# WX0_008_511DL_4.net
KiCad netlist of a schematic drawn in Altium Designer
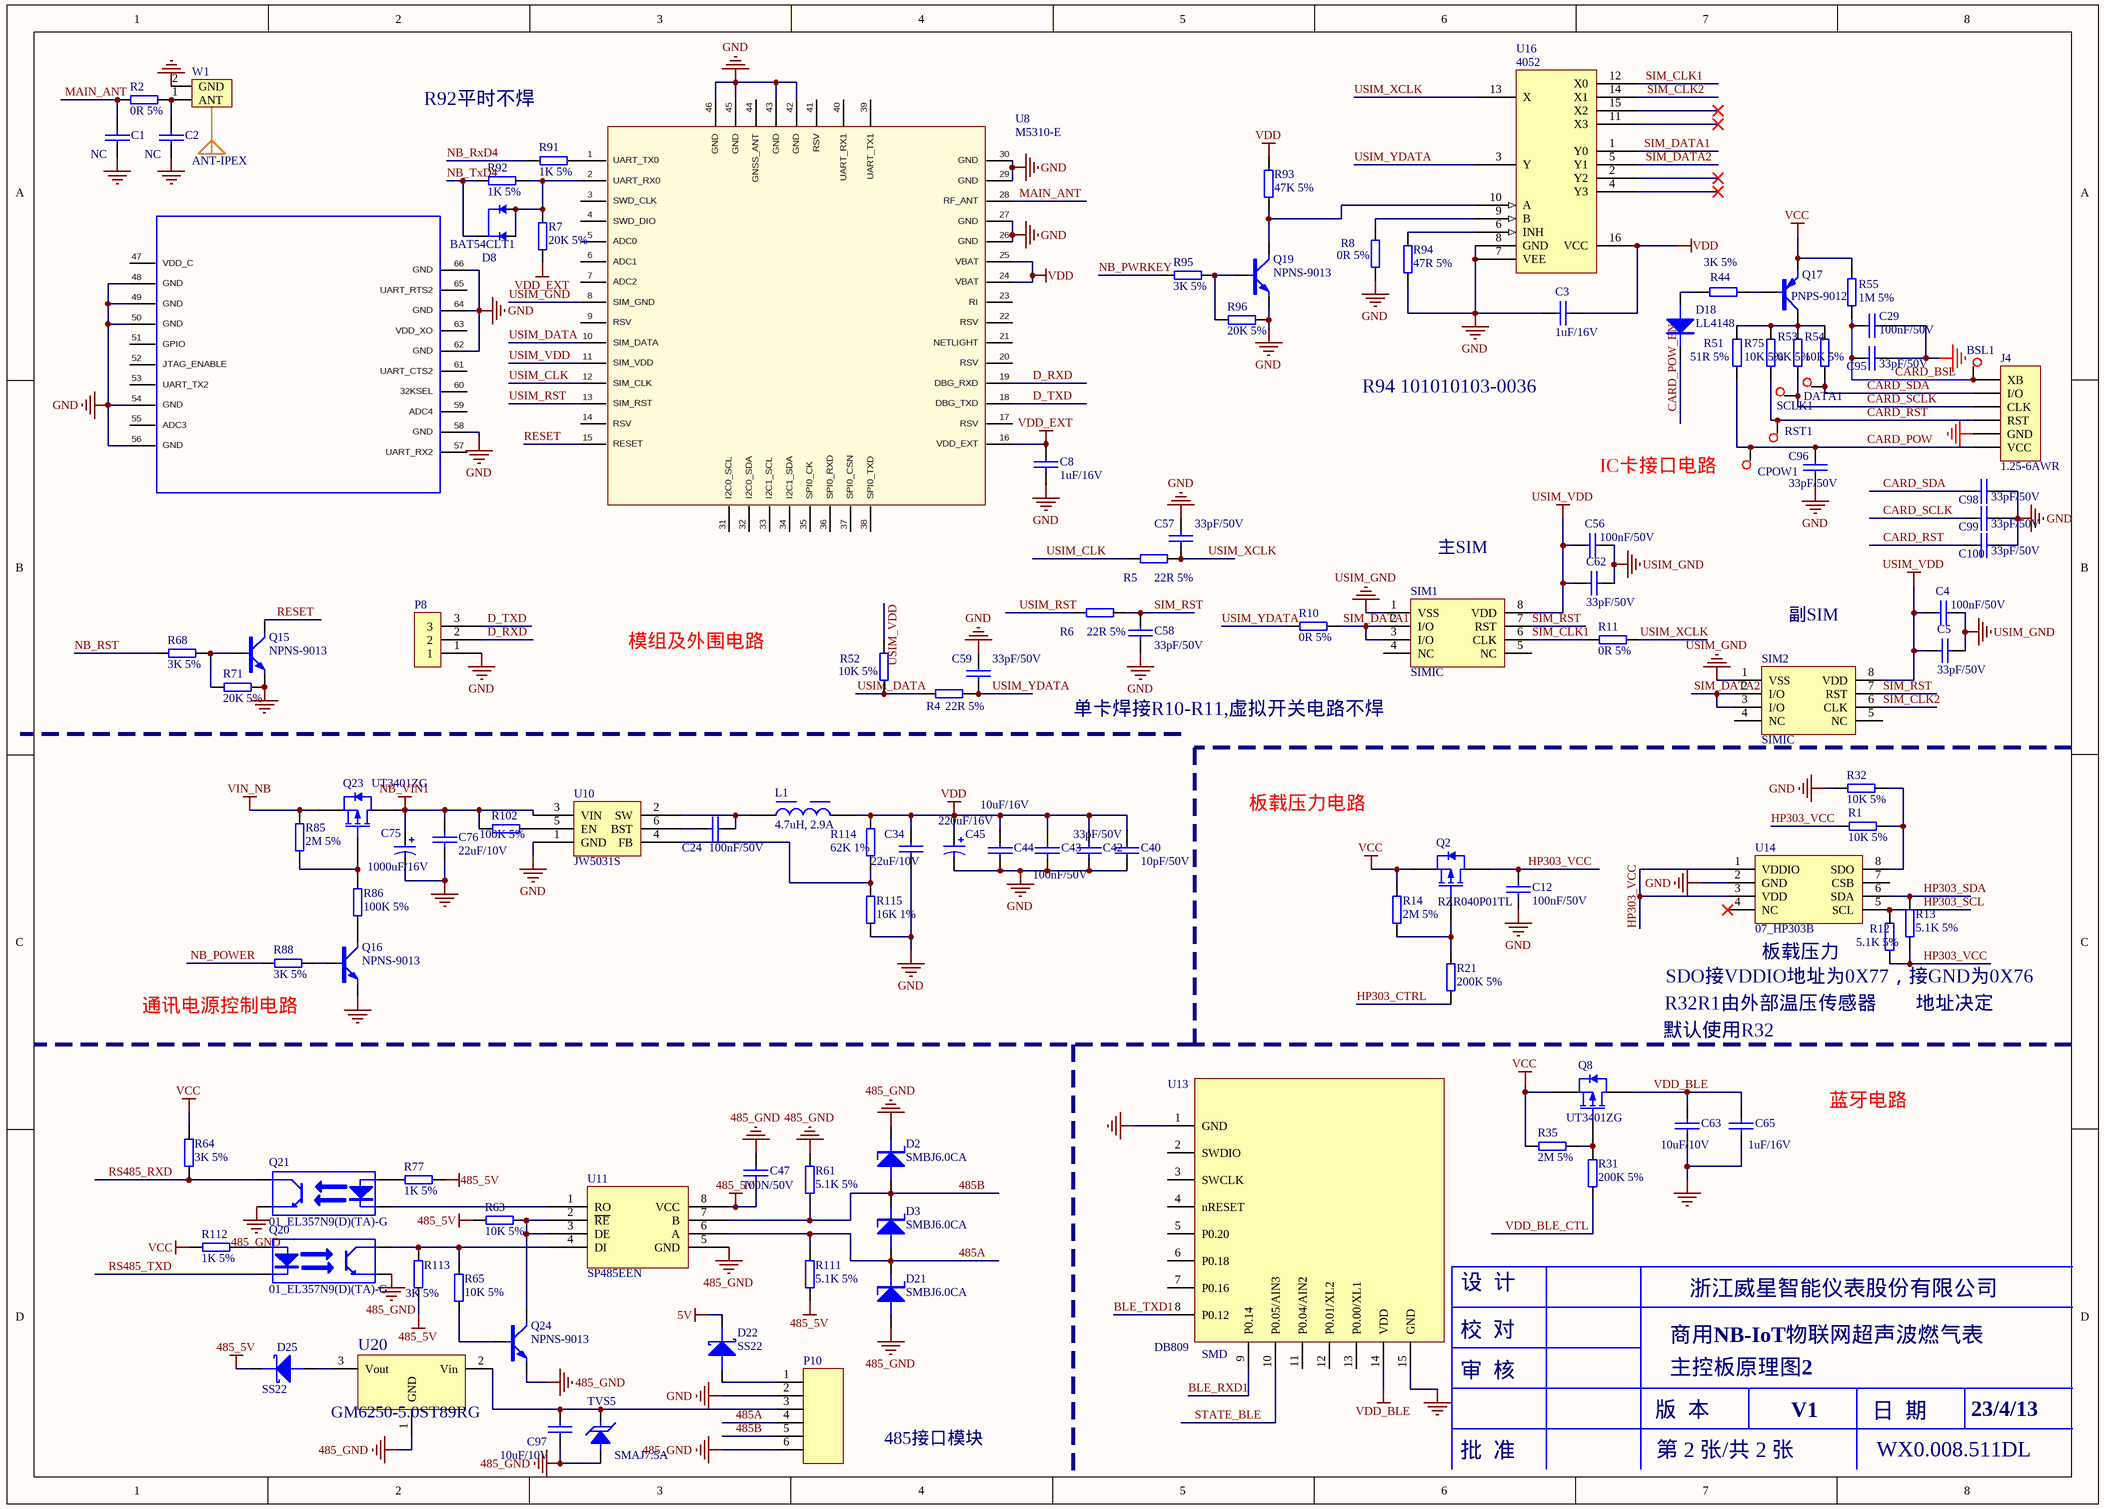
[diagram p0: WX0.008.511DL(4).SchDoc]

(export (version "E")
  (design (tool "Eeschema 10.0.6"))
  (components
    (comp (ref "BSL1")
      (value "TEST-PAD")
      (footprint "TEST-PAD")
      (description "单面焊盘测试点")
      (fields (field (name "PART NUMBER") "AD_WXHJ_TEST-PAD_01"))
      (libsource (lib "Database_Libs2") (part "TEST-PAD"))
    )
    (comp (ref "C1")
      (value "NC")
      (footprint "CAP0603")
      (description "104pF,50 V,±10%,0603,国巨,CC0603KRX7R9BB104")
      (fields (field (name "PART NUMBER") "101020103-0021"))
      (libsource (lib "Database_Libs2") (part "CC03K7R9_100N"))
    )
    (comp (ref "C2")
      (value "NC")
      (footprint "CAP0603")
      (description "104pF,50 V,±10%,0603,国巨,CC0603KRX7R9BB104")
      (fields (field (name "PART NUMBER") "101020103-0021"))
      (libsource (lib "Database_Libs2") (part "CC03K7R9_100N"))
    )
    (comp (ref "C3")
      (value "1uF/16V")
      (footprint "CAP0603")
      (description "105pF,16 V,±10%,0603,国巨,CC0603KRX7R7BB105")
      (fields (field (name "PART NUMBER") "101020103-0003"))
      (libsource (lib "Database_Libs2") (part "CC03K7R7_1U"))
    )
    (comp (ref "C4")
      (value "100nF/50V")
      (footprint "CAP0603")
      (description "104pF,50 V,±10%,0603,国巨,CC0603KRX7R9BB104")
      (fields (field (name "PART NUMBER") "101020103-0021"))
      (libsource (lib "Database_Libs2") (part "CC03K7R9_100N"))
    )
    (comp (ref "C5")
      (value "33pF/50V")
      (footprint "CAP0603")
      (description "33pF,50 V,±10%,0603,国巨,CC0603KRNPO9BN33")
      (fields (field (name "PART NUMBER") "101020103-0027"))
      (libsource (lib "Database_Libs2") (part "CC03KPO9_33P"))
    )
    (comp (ref "C8")
      (value "1uF/16V")
      (footprint "CAP0603")
      (description "105pF,16 V,±10%,0603,国巨,CC0603KRX7R7BB105")
      (fields (field (name "PART NUMBER") "101020103-0003"))
      (libsource (lib "Database_Libs2") (part "CC03K7R7_1U"))
    )
    (comp (ref "C12")
      (value "100nF/50V")
      (footprint "CAP0603")
      (description "104pF,50 V,±10%,0603,国巨,CC0603KRX7R9BB104")
      (fields (field (name "PART NUMBER") "101020103-0021"))
      (libsource (lib "Database_Libs2") (part "CC03K7R9_100N"))
    )
    (comp (ref "C24")
      (value "100nF/50V")
      (footprint "CAP0603")
      (description "104pF,50 V,±10%,0603,国巨,CC0603KRX7R9BB104")
      (fields (field (name "PART NUMBER") "101020103-0021"))
      (libsource (lib "Database_Libs2") (part "CC03K7R9_100N"))
    )
    (comp (ref "C29")
      (value "100nF/50V")
      (footprint "CAP0603")
      (description "104pF,50 V,±10%,0603,国巨,CC0603KRX7R9BB104")
      (fields (field (name "PART NUMBER") "101020103-0021"))
      (libsource (lib "Database_Libs2") (part "CC03K7R9_100N"))
    )
    (comp (ref "C34")
      (value "22uF/10V")
      (footprint "CAP0805")
      (description "226P,10 V,±20%,0805,村田电子有限公司,GRM21BR61A226ME51L")
      (fields (field (name "PART NUMBER") "101020102-0012"))
      (libsource (lib "Database_Libs2") (part "CC05M5R6_226P"))
    )
    (comp (ref "C40")
      (value "10pF/50V")
      (footprint "CAP0603")
      (description "10pF,50 V,±5%,0603,X7R,国巨,CC0603JRNPO9BN100")
      (fields (field (name "PART NUMBER") "101020103-0014"))
      (libsource (lib "Database_Libs2") (part "CC03JPO9_10P"))
    )
    (comp (ref "C42")
      (value "33pF/50V")
      (footprint "CAP0603")
      (description "33pF,50 V,±10%,0603,国巨,CC0603KRNPO9BN33")
      (fields (field (name "PART NUMBER") "101020103-0027"))
      (libsource (lib "Database_Libs2") (part "CC03KPO9_33P"))
    )
    (comp (ref "C43")
      (value "100nF/50V")
      (footprint "CAP0603")
      (description "104pF,50 V,±10%,0603,国巨,CC0603KRX7R9BB104")
      (fields (field (name "PART NUMBER") "101020103-0021"))
      (libsource (lib "Database_Libs2") (part "CC03K7R9_100N"))
    )
    (comp (ref "C44")
      (value "10uF/16V")
      (footprint "CAP1206")
      (description "106P,16 V,±10%,1206,国巨,CC1206KRNPO7BN106P")
      (fields (field (name "PART NUMBER") "101020101-0005"))
      (libsource (lib "Database_Libs2") (part "CC06KPO7_106P"))
    )
    (comp (ref "C45")
      (value "220uF/16V")
      (footprint "220uf/16V")
      (description "1000uF,16 V,±20%,8*20mm,Rubycon,16ZLH1000M")
      (fields (field (name "PART NUMBER") "1010203-0029"))
      (libsource (lib "Database_Libs2") (part "CAL7MRZLH_1000U_R"))
    )
    (comp (ref "C47")
      (value "100N/50V")
      (footprint "CAP0603")
      (description "100N/50V，±10%，0603")
      (fields (field (name "PART NUMBER") "101020103-0021"))
      (libsource (lib "Database_Libs1") (part "CC03K7R9B_100N"))
    )
    (comp (ref "C56")
      (value "100nF/50V")
      (footprint "CAP0603")
      (description "104pF,50 V,±10%,0603,国巨,CC0603KRX7R9BB104")
      (fields (field (name "PART NUMBER") "101020103-0021"))
      (libsource (lib "Database_Libs2") (part "CC03K7R9_100N"))
    )
    (comp (ref "C57")
      (value "33pF/50V")
      (footprint "CAP0603")
      (description "33pF,50 V,±10%,0603,国巨,CC0603KRNPO9BN33")
      (fields (field (name "PART NUMBER") "101020103-0027"))
      (libsource (lib "Database_Libs2") (part "CC03KPO9_33P"))
    )
    (comp (ref "C58")
      (value "33pF/50V")
      (footprint "CAP0603")
      (description "33pF,50 V,±10%,0603,国巨,CC0603KRNPO9BN33")
      (fields (field (name "PART NUMBER") "101020103-0027"))
      (libsource (lib "Database_Libs2") (part "CC03KPO9_33P"))
    )
    (comp (ref "C59")
      (value "33pF/50V")
      (footprint "CAP0603")
      (description "33pF,50 V,±10%,0603,国巨,CC0603KRNPO9BN33")
      (fields (field (name "PART NUMBER") "101020103-0027"))
      (libsource (lib "Database_Libs2") (part "CC03KPO9_33P"))
    )
    (comp (ref "C62")
      (value "33pF/50V")
      (footprint "CAP0603")
      (description "33pF,50 V,±10%,0603,国巨,CC0603KRNPO9BN33")
      (fields (field (name "PART NUMBER") "101020103-0027"))
      (libsource (lib "Database_Libs2") (part "CC03KPO9_33P"))
    )
    (comp (ref "C63")
      (value "10uF/10V")
      (footprint "CAP0603")
      (description "106pF,10 V,±10%,0603,村田,GRM188R61A106KE47D")
      (fields (field (name "PART NUMBER") "101020103-0026"))
      (libsource (lib "Database_Libs2") (part "CC03K5R6_10U"))
    )
    (comp (ref "C65")
      (value "1uF/16V")
      (footprint "CAP0603")
      (description "105pF,16 V,±10%,0603,国巨,CC0603KRX7R7BB105")
      (fields (field (name "PART NUMBER") "101020103-0003"))
      (libsource (lib "Database_Libs2") (part "CC03K7R7_1U"))
    )
    (comp (ref "C75")
      (value "1000uF/16V")
      (footprint "CAP-SMD_BD10.0-L10.3-W10.3-FD")
      (description "1000uF,16 V,±20%,8*20mm,Rubycon,16ZLH1000M")
      (fields (field (name "PART NUMBER") "1010203-0029"))
      (libsource (lib "Database_Libs2") (part "CAL7MRZLH_1000U_R"))
    )
    (comp (ref "C76")
      (value "22uF/10V")
      (footprint "CAP0805")
      (description "226P,10 V,±20%,0805,村田电子有限公司,GRM21BR61A226ME51L")
      (fields (field (name "PART NUMBER") "101020102-0012"))
      (libsource (lib "Database_Libs2") (part "CC05M5R6_226P"))
    )
    (comp (ref "C95")
      (value "33pF/50V")
      (footprint "CAP0603")
      (description "33pF,50 V,±10%,0603,国巨,CC0603KRNPO9BN33")
      (fields (field (name "PART NUMBER") "101020103-0027"))
      (libsource (lib "Database_Libs2") (part "CC03KPO9_33P"))
    )
    (comp (ref "C96")
      (value "33pF/50V")
      (footprint "CAP0603")
      (description "33pF,50 V,±10%,0603,国巨,CC0603KRNPO9BN33")
      (fields (field (name "PART NUMBER") "101020103-0027"))
      (libsource (lib "Database_Libs2") (part "CC03KPO9_33P"))
    )
    (comp (ref "C97")
      (value "10uF/10V")
      (footprint "CAP0603")
      (description "106pF,10 V,±10%,0603,村田,GRM188R61A106KE47D")
      (fields (field (name "PART NUMBER") "101020103-0026"))
      (libsource (lib "Database_Libs2") (part "CC03K5R6_10U"))
    )
    (comp (ref "C98")
      (value "33pF/50V")
      (footprint "CAP0603")
      (description "33pF,50 V,±10%,0603,国巨,CC0603KRNPO9BN33")
      (fields (field (name "PART NUMBER") "101020103-0027"))
      (libsource (lib "Database_Libs2") (part "CC03KPO9_33P"))
    )
    (comp (ref "C99")
      (value "33pF/50V")
      (footprint "CAP0603")
      (description "33pF,50 V,±10%,0603,国巨,CC0603KRNPO9BN33")
      (fields (field (name "PART NUMBER") "101020103-0027"))
      (libsource (lib "Database_Libs2") (part "CC03KPO9_33P"))
    )
    (comp (ref "C100")
      (value "33pF/50V")
      (footprint "CAP0603")
      (description "33pF,50 V,±10%,0603,国巨,CC0603KRNPO9BN33")
      (fields (field (name "PART NUMBER") "101020103-0027"))
      (libsource (lib "Database_Libs2") (part "CC03KPO9_33P"))
    )
    (comp (ref "CPOW1")
      (value "TEST-PAD")
      (footprint "TEST-PAD")
      (description "单面焊盘测试点")
      (fields (field (name "PART NUMBER") "AD_WXHJ_TEST-PAD_01"))
      (libsource (lib "Database_Libs2") (part "TEST-PAD"))
    )
    (comp (ref "D2")
      (value "SMBJ6.0CA")
      (footprint "5025D")
      (description "SMBJ6.0CA，6V单向TVS管")
      (fields (field (name "PART NUMBER") "101040101-0024"))
      (libsource (lib "Database_Libs1") (part "SMBJ6.0CA"))
    )
    (comp (ref "D3")
      (value "SMBJ6.0CA")
      (footprint "5025D")
      (description "SMBJ6.0CA，6V单向TVS管")
      (fields (field (name "PART NUMBER") "101040101-0024"))
      (libsource (lib "Database_Libs1") (part "SMBJ6.0CA"))
    )
    (comp (ref "D8")
      (value "BAT54CLT1")
      (footprint "SOT-23")
      (description "BAT54CLT1，SOT23-3,SOT23-3,0.2 A,0.8 V,30 V,安森美,BAT54CLT1")
      (fields (field (name "PART NUMBER") "101040101-0038"))
      (libsource (lib "Database_Libs2") (part "02_BAT54CLT1"))
    )
    (comp (ref "D18")
      (value "LL4148")
      (footprint "SOD-123FL")
      (description "4148,4148,0.2 A,1 V,100 V,先科,LL4148")
      (fields (field (name "PART NUMBER") "101040101-0005"))
      (libsource (lib "Database_Libs2") (part "02_LL4148"))
    )
    (comp (ref "D21")
      (value "SMBJ6.0CA")
      (footprint "5025D")
      (description "SMBJ6.0CA，6V单向TVS管")
      (fields (field (name "PART NUMBER") "101040101-0024"))
      (libsource (lib "Database_Libs1") (part "SMBJ6.0CA"))
    )
    (comp (ref "D22")
      (value "SS22")
      (footprint "DO-214AC")
      (description "DS36W,SOD123-FL,3 A,42 V,60 V,浙江领晨科技有限公司,DS36W")
      (fields (field (name "PART NUMBER") "101040101-0055"))
      (libsource (lib "Database_Libs2") (part "02_DS36W"))
    )
    (comp (ref "D25")
      (value "SS22")
      (footprint "DO-214AC")
      (description "DS36W,SOD123-FL,3 A,42 V,60 V,浙江领晨科技有限公司,DS36W")
      (fields (field (name "PART NUMBER") "101040101-0055"))
      (libsource (lib "Database_Libs2") (part "02_DS36W"))
    )
    (comp (ref "DATA1")
      (value "TEST-PAD")
      (footprint "TEST-PAD")
      (description "单面焊盘测试点")
      (fields (field (name "PART NUMBER") "AD_WXHJ_TEST-PAD_01"))
      (libsource (lib "Database_Libs2") (part "TEST-PAD"))
    )
    (comp (ref "J4")
      (value "1.25-6AWR")
      (footprint "SMT-1.25-6")
      (description "1.25-6AWR 卷,6针1.25mm,母头,单排,贴片卧式")
      (fields (field (name "PART NUMBER") "1010902-0121"))
      (libsource (lib "Database_Libs2") (part "CARD1608"))
    )
    (comp (ref "L1")
      (value "4.7uH, 2.9A")
      (footprint "WE-MAPI_4020")
      (description "WE-MAPI SMT Power Inductor, size 4020, 4.7uH, 2.9A")
      (fields
        (field (name "MANUFACTURER") "Wurth Elektronik")
        (field (name "MANUFACTURER PART NUMBER") "74438356047")
      )
      (libsource (lib "WE-MAPI (rev20b)") (part "74438356047"))
    )
    (comp (ref "P8")
      (value "Component_2")
      (footprint "PCBComponent_1 - duplicate")
      (libsource (lib "Schlib1") (part "Component_2"))
    )
    (comp (ref "P10")
      (value "~")
      (footprint "6Pin插座")
      (fields (field (name "PART NUMBER") "1010902-0119"))
      (libsource (lib "Database_Libs1") (part "MicroUSB-AFR"))
    )
    (comp (ref "Q2")
      (value "RZR040P01TL")
      (footprint "SOT-23")
      (description "RZR040P01TL；1.5v导通,P-MOS,SOT-23,罗姆,RZR040P01TL")
      (fields (field (name "PART NUMBER") "101040201-0010"))
      (libsource (lib "Database_Libs2") (part "03_P-RZR040P01TL"))
    )
    (comp (ref "Q8")
      (value "UT3401ZG")
      (footprint "SOT-23")
      (description "UT3401ZG,P-MOS,SOT-23,UTC,UT3401ZG")
      (fields (field (name "PART NUMBER") "101040201-0013"))
      (libsource (lib "Database_Libs2") (part "03_P-UT3401ZG"))
    )
    (comp (ref "Q15")
      (value "NPNS-9013")
      (footprint "SOT-23")
      (description "9013,NPN,SOT-23,长电,S9013")
      (fields (field (name "PART NUMBER") "101040201-0002"))
      (libsource (lib "Database_Libs2") (part "03_NPNS-9013"))
    )
    (comp (ref "Q16")
      (value "NPNS-9013")
      (footprint "SOT-23")
      (description "9013,NPN,SOT-23,长电,S9013")
      (fields (field (name "PART NUMBER") "101040201-0002"))
      (libsource (lib "Database_Libs2") (part "03_NPNS-9013"))
    )
    (comp (ref "Q17")
      (value "PNPS-9012")
      (footprint "SOT-23")
      (description "9012,PNP,SOT-23,JCET;长电,S9012")
      (fields (field (name "PART NUMBER") "101040201-0001"))
      (libsource (lib "Database_Libs2") (part "03_PNPS-9012"))
    )
    (comp (ref "Q19")
      (value "NPNS-9013")
      (footprint "SOT-23")
      (description "9013,NPN,SOT-23,长电,S9013")
      (fields (field (name "PART NUMBER") "101040201-0002"))
      (libsource (lib "Database_Libs2") (part "03_NPNS-9013"))
    )
    (comp (ref "Q20")
      (value "01_EL357N9(D)(TA)-G")
      (footprint "EL357D")
      (fields (field (name "PART NUMBER") "1010502-0045"))
      (libsource (lib "Database_Libs1") (part "01_EL357N9(D)(TA)-G"))
    )
    (comp (ref "Q21")
      (value "01_EL357N9(D)(TA)-G")
      (footprint "EL357D")
      (fields (field (name "PART NUMBER") "1010502-0045"))
      (libsource (lib "Database_Libs1") (part "01_EL357N9(D)(TA)-G"))
    )
    (comp (ref "Q23")
      (value "UT3401ZG")
      (footprint "SOT-23")
      (description "UT3401ZG,P-MOS,SOT-23,UTC,UT3401ZG")
      (fields (field (name "PART NUMBER") "101040201-0013"))
      (libsource (lib "Database_Libs2") (part "03_P-UT3401ZG"))
    )
    (comp (ref "Q24")
      (value "NPNS-9013")
      (footprint "SOT-23")
      (description "9013,NPN,SOT-23,长电,S9013")
      (fields (field (name "PART NUMBER") "101040201-0002"))
      (libsource (lib "Database_Libs2") (part "03_NPNS-9013"))
    )
    (comp (ref "R1")
      (value "10K 5%")
      (footprint "RES0603")
      (description "国巨,±5%,0603,,155 ℃,-55 ℃,RC0603JR-071ML,无铅,200 ppm/℃,1/10W,,1M")
      (fields (field (name "PART NUMBER") "101010103-0002"))
      (libsource (lib "Database_Libs2") (part "RC03J_1M"))
    )
    (comp (ref "R2")
      (value "0R 5%")
      (footprint "RES0603")
      (description "国巨,±5%,0603,,155 ℃,-55 ℃,RC0603J2-070RL,无铅,200 ppm/℃,1/10W,,0R")
      (fields (field (name "PART NUMBER") "101010103-0001"))
      (libsource (lib "Database_Libs2") (part "RC03J_0R"))
    )
    (comp (ref "R4")
      (value "22R 5%")
      (footprint "RES0603")
      (description "国巨,±5%,0603,,155 ℃,-55 ℃,RC0603JR-0722RL,无铅,200 ppm/℃,1/10W,,22欧")
      (fields (field (name "PART NUMBER") "101010103-0009"))
      (libsource (lib "Database_Libs2") (part "RC03J_22R"))
    )
    (comp (ref "R5")
      (value "22R 5%")
      (footprint "RES0603")
      (description "国巨,±5%,0603,,155 ℃,-55 ℃,RC0603JR-0722RL,无铅,200 ppm/℃,1/10W,,22欧")
      (fields (field (name "PART NUMBER") "101010103-0009"))
      (libsource (lib "Database_Libs2") (part "RC03J_22R"))
    )
    (comp (ref "R6")
      (value "22R 5%")
      (footprint "RES0603")
      (description "国巨,±5%,0603,,155 ℃,-55 ℃,RC0603JR-0722RL,无铅,200 ppm/℃,1/10W,,22欧")
      (fields (field (name "PART NUMBER") "101010103-0009"))
      (libsource (lib "Database_Libs2") (part "RC03J_22R"))
    )
    (comp (ref "R7")
      (value "20K 5%")
      (footprint "RES0603")
      (description "国巨,±5%,0603,,155 ℃,-55 ℃,RC0603JR-0720KL,无铅,200 ppm/℃,1/10W,,20K")
      (fields (field (name "PART NUMBER") "101010103-0004"))
      (libsource (lib "Database_Libs2") (part "RC03J_20K"))
    )
    (comp (ref "R8")
      (value "0R 5%")
      (footprint "RES0603")
      (description "国巨,±5%,0603,,155 ℃,-55 ℃,RC0603J2-070RL,无铅,200 ppm/℃,1/10W,,0R")
      (fields (field (name "PART NUMBER") "101010103-0001"))
      (libsource (lib "Database_Libs2") (part "RC03J_0R"))
    )
    (comp (ref "R10")
      (value "0R 5%")
      (footprint "RES0603")
      (description "国巨,±5%,0603,,155 ℃,-55 ℃,RC0603J2-070RL,无铅,200 ppm/℃,1/10W,,0R")
      (fields (field (name "PART NUMBER") "101010103-0001"))
      (libsource (lib "Database_Libs2") (part "RC03J_0R"))
    )
    (comp (ref "R11")
      (value "0R 5%")
      (footprint "RES0603")
      (description "国巨,±5%,0603,,155 ℃,-55 ℃,RC0603J2-070RL,无铅,200 ppm/℃,1/10W,,0R")
      (fields (field (name "PART NUMBER") "101010103-0001"))
      (libsource (lib "Database_Libs2") (part "RC03J_0R"))
    )
    (comp (ref "R12")
      (value "5.1K 5%")
      (footprint "RES0603")
      (description "国巨,±5%,0603,,155 ℃,55 ℃,RC0603JR-075.1KL,无铅,200 ppm/℃,1/10W,,5.1k")
      (fields (field (name "PART NUMBER") "101010103-0015"))
      (libsource (lib "Database_Libs2") (part "RC03J_5.1K"))
    )
    (comp (ref "R13")
      (value "5.1K 5%")
      (footprint "RES0603")
      (description "国巨,±5%,0603,,155 ℃,55 ℃,RC0603JR-075.1KL,无铅,200 ppm/℃,1/10W,,5.1k")
      (fields (field (name "PART NUMBER") "101010103-0015"))
      (libsource (lib "Database_Libs2") (part "RC03J_5.1K"))
    )
    (comp (ref "R14")
      (value "2M 5%")
      (footprint "RES0603")
      (description "国巨,±5%,0603,,155 ℃,-55 ℃,RC0603JR-072ML,含铅,100 ppm/℃,1/10W,,2M")
      (fields (field (name "PART NUMBER") "101010103-0025"))
      (libsource (lib "Database_Libs2") (part "RC03J_2M"))
    )
    (comp (ref "R21")
      (value "200K 5%")
      (footprint "RES0603")
      (description "200K,±5%,1/10W,0603,国巨,RC0603JR-07200KL")
      (fields (field (name "PART NUMBER") "101010103-0034"))
      (libsource (lib "Database_Libs2") (part "RC03J_200K"))
    )
    (comp (ref "R31")
      (value "200K 5%")
      (footprint "RES0603")
      (description "10K±5%,1/10W,0603")
      (fields (field (name "PART NUMBER") "101010103-0003"))
      (libsource (lib "Database_Libs1") (part "RC03JF_10K"))
    )
    (comp (ref "R32")
      (value "10K 5%")
      (footprint "RES0603")
      (description "国巨,±5%,0603,,155 ℃,-55 ℃,RC0603JR-071ML,无铅,200 ppm/℃,1/10W,,1M")
      (fields (field (name "PART NUMBER") "101010103-0002"))
      (libsource (lib "Database_Libs2") (part "RC03J_1M"))
    )
    (comp (ref "R35")
      (value "2M 5%")
      (footprint "RES0603")
      (description "10K±5%,1/10W,0603")
      (fields (field (name "PART NUMBER") "101010103-0003"))
      (libsource (lib "Database_Libs1") (part "RC03JF_10K"))
    )
    (comp (ref "R44")
      (value "3K 5%")
      (footprint "RES0603")
      (description "国巨,±5%,0603,,155 ℃,-55 ℃,RC0603JR-073KL,无铅,100 ppm/℃,1/10W,,3K")
      (fields (field (name "PART NUMBER") "101010103-0006"))
      (libsource (lib "Database_Libs2") (part "RC03J_3K"))
    )
    (comp (ref "R51")
      (value "51R 5%")
      (footprint "RES1206")
      (description "51Ω,±5%,1/4W,1206,国巨,RC1206JR-0751RL")
      (fields (field (name "PART NUMBER") "101010101-0029"))
      (libsource (lib "Database_Libs2") (part "RC06F_51R"))
    )
    (comp (ref "R52")
      (value "10K 5%")
      (footprint "RES0603")
      (description "国巨,±5%,0603,,155 ℃,-55 ℃,RC0603JR-0710KL,无铅,200 ppm/℃,1/10W,,10K")
      (fields (field (name "PART NUMBER") "101010103-0003"))
      (libsource (lib "Database_Libs2") (part "RC03J_10K"))
    )
    (comp (ref "R53")
      (value "10K 5%")
      (footprint "RES0603")
      (description "国巨,±5%,0603,,155 ℃,-55 ℃,RC0603JR-0710KL,无铅,200 ppm/℃,1/10W,,10K")
      (fields (field (name "PART NUMBER") "101010103-0003"))
      (libsource (lib "Database_Libs2") (part "RC03J_10K"))
    )
    (comp (ref "R54")
      (value "10K 5%")
      (footprint "RES0603")
      (description "国巨,±5%,0603,,155 ℃,-55 ℃,RC0603JR-0710KL,无铅,200 ppm/℃,1/10W,,10K")
      (fields (field (name "PART NUMBER") "101010103-0003"))
      (libsource (lib "Database_Libs2") (part "RC03J_10K"))
    )
    (comp (ref "R55")
      (value "1M 5%")
      (footprint "RES0603")
      (description "国巨,±5%,0603,,155 ℃,-55 ℃,RC0603JR-071ML,无铅,200 ppm/℃,1/10W,,1M")
      (fields (field (name "PART NUMBER") "101010103-0002"))
      (libsource (lib "Database_Libs2") (part "RC03J_1M"))
    )
    (comp (ref "R61")
      (value "5.1K 5%")
      (footprint "RES0603")
      (description "5.1K±5%,1/10W,0603")
      (fields (field (name "PART NUMBER") "101010103-0015"))
      (libsource (lib "Database_Libs1") (part "RC03JF_5.1K"))
    )
    (comp (ref "R63")
      (value "10K 5%")
      (footprint "RES0603")
      (description "10K±5%,1/10W,0603")
      (fields (field (name "PART NUMBER") "101010103-0003"))
      (libsource (lib "Database_Libs1") (part "RC03JF_10K"))
    )
    (comp (ref "R64")
      (value "3K 5%")
      (footprint "RES0603")
      (description "3K±5%,1/10W,0603")
      (fields (field (name "PART NUMBER") "101010103-0006"))
      (libsource (lib "Database_Libs1") (part "RC03JF_3K"))
    )
    (comp (ref "R65")
      (value "10K 5%")
      (footprint "RES0603")
      (description "10K±5%,1/10W,0603")
      (fields (field (name "PART NUMBER") "101010103-0003"))
      (libsource (lib "Database_Libs1") (part "RC03JF_10K"))
    )
    (comp (ref "R68")
      (value "3K 5%")
      (footprint "RES0603")
      (description "国巨,±5%,0603,,155 ℃,-55 ℃,RC0603JR-073KL,无铅,100 ppm/℃,1/10W,,3K")
      (fields (field (name "PART NUMBER") "101010103-0006"))
      (libsource (lib "Database_Libs2") (part "RC03J_3K"))
    )
    (comp (ref "R71")
      (value "20K 5%")
      (footprint "RES0603")
      (description "国巨,±5%,0603,,155 ℃,-55 ℃,RC0603JR-0720KL,无铅,200 ppm/℃,1/10W,,20K")
      (fields (field (name "PART NUMBER") "101010103-0004"))
      (libsource (lib "Database_Libs2") (part "RC03J_20K"))
    )
    (comp (ref "R75")
      (value "10K 5%")
      (footprint "RES0603")
      (description "国巨,±5%,0603,,155 ℃,-55 ℃,RC0603JR-0710KL,无铅,200 ppm/℃,1/10W,,10K")
      (fields (field (name "PART NUMBER") "101010103-0003"))
      (libsource (lib "Database_Libs2") (part "RC03J_10K"))
    )
    (comp (ref "R77")
      (value "1K 5%")
      (footprint "RES0603")
      (description "1K±5%,1/10W,0603")
      (fields (field (name "PART NUMBER") "101010103-0008"))
      (libsource (lib "Database_Libs1") (part "RC03JF_1K"))
    )
    (comp (ref "R85")
      (value "2M 5%")
      (footprint "RES0603")
      (description "国巨,±5%,0603,,155 ℃,-55 ℃,RC0603JR-072ML,含铅,100 ppm/℃,1/10W,,2M")
      (fields (field (name "PART NUMBER") "101010103-0025"))
      (libsource (lib "Database_Libs2") (part "RC03J_2M"))
    )
    (comp (ref "R86")
      (value "100K 5%")
      (footprint "RES0603")
      (description "国巨,±5%,0603,,155 ℃,-55 ℃,RC0603JR-07100KL,无铅,100 ppm/℃,1/10W,,100K")
      (fields (field (name "PART NUMBER") "101010103-0005"))
      (libsource (lib "Database_Libs2") (part "RC03J_100K"))
    )
    (comp (ref "R88")
      (value "3K 5%")
      (footprint "RES0603")
      (description "国巨,±5%,0603,,155 ℃,-55 ℃,RC0603JR-073KL,无铅,100 ppm/℃,1/10W,,3K")
      (fields (field (name "PART NUMBER") "101010103-0006"))
      (libsource (lib "Database_Libs2") (part "RC03J_3K"))
    )
    (comp (ref "R91")
      (value "1K 5%")
      (footprint "RES0603")
      (description "1K,±5%,1/10W,0603,国巨,RC0603JR-071KL")
      (fields (field (name "PART NUMBER") "101010103-0008"))
      (libsource (lib "Database_Libs2") (part "RC03J_1K"))
    )
    (comp (ref "R92")
      (value "1K 5%")
      (footprint "RES0603")
      (description "1K,±5%,1/10W,0603,国巨,RC0603JR-071KL")
      (fields (field (name "PART NUMBER") "101010103-0008"))
      (libsource (lib "Database_Libs2") (part "RC03J_1K"))
    )
    (comp (ref "R93")
      (value "47K 5%")
      (footprint "RES0603")
      (description "47K,±5%,1/10W,0603,国巨,RC0603JR-0747KL")
      (fields (field (name "PART NUMBER") "101010103-0012"))
      (libsource (lib "Database_Libs2") (part "RC03J_47K"))
    )
    (comp (ref "R94")
      (value "47R 5%")
      (footprint "RES0603")
      (description "国巨,±5%,0603,,155 ℃,-55 ℃,RC0603JR-0722RL,无铅,200 ppm/℃,1/10W,,22欧")
      (fields (field (name "PART NUMBER") "101010103-0009"))
      (libsource (lib "Database_Libs2") (part "RC03J_22R"))
    )
    (comp (ref "R95")
      (value "3K 5%")
      (footprint "RES0603")
      (description "国巨,±5%,0603,,155 ℃,-55 ℃,RC0603JR-073KL,无铅,100 ppm/℃,1/10W,,3K")
      (fields (field (name "PART NUMBER") "101010103-0006"))
      (libsource (lib "Database_Libs2") (part "RC03J_3K"))
    )
    (comp (ref "R96")
      (value "20K 5%")
      (footprint "RES0603")
      (description "国巨,±5%,0603,,155 ℃,-55 ℃,RC0603JR-0720KL,无铅,200 ppm/℃,1/10W,,20K")
      (fields (field (name "PART NUMBER") "101010103-0004"))
      (libsource (lib "Database_Libs2") (part "RC03J_20K"))
    )
    (comp (ref "R102")
      (value "100K 5%")
      (footprint "RES0603")
      (description "国巨,±5%,0603,,155 ℃,-55 ℃,RC0603JR-07100KL,无铅,100 ppm/℃,1/10W,,100K")
      (fields (field (name "PART NUMBER") "101010103-0005"))
      (libsource (lib "Database_Libs2") (part "RC03J_100K"))
    )
    (comp (ref "R111")
      (value "5.1K 5%")
      (footprint "RES0603")
      (description "5.1K±5%,1/10W,0603")
      (fields (field (name "PART NUMBER") "101010103-0015"))
      (libsource (lib "Database_Libs1") (part "RC03JF_5.1K"))
    )
    (comp (ref "R112")
      (value "1K 5%")
      (footprint "RES0603")
      (description "1K±5%,1/10W,0603")
      (fields (field (name "PART NUMBER") "101010103-0008"))
      (libsource (lib "Database_Libs1") (part "RC03JF_1K"))
    )
    (comp (ref "R113")
      (value "3K 5%")
      (footprint "RES0603")
      (description "3K±5%,1/10W,0603")
      (fields (field (name "PART NUMBER") "101010103-0006"))
      (libsource (lib "Database_Libs1") (part "RC03JF_3K"))
    )
    (comp (ref "R114")
      (value "62K 1%")
      (footprint "RES0603")
      (description "国巨,±5%,0603,,155 ℃,-55 ℃,RC0603JR,含铅,100 ppm/℃,1/10W,,22k")
      (fields (field (name "PART NUMBER") "101010103-0067"))
      (libsource (lib "Database_Libs2") (part "RC03J_22K"))
    )
    (comp (ref "R115")
      (value "16K 1%")
      (footprint "RES0603")
      (description "国巨,±5%,0603,,155 ℃,-55 ℃,RC0603JR-0710KL,无铅,200 ppm/℃,1/10W,,10K")
      (fields (field (name "PART NUMBER") "101010103-0003"))
      (libsource (lib "Database_Libs2") (part "RC03J_10K"))
    )
    (comp (ref "RST1")
      (value "TEST-PAD")
      (footprint "TEST-PAD")
      (description "单面焊盘测试点")
      (fields (field (name "PART NUMBER") "AD_WXHJ_TEST-PAD_01"))
      (libsource (lib "Database_Libs2") (part "TEST-PAD"))
    )
    (comp (ref "SCLK1")
      (value "TEST-PAD")
      (footprint "TEST-PAD")
      (description "单面焊盘测试点")
      (fields (field (name "PART NUMBER") "AD_WXHJ_TEST-PAD_01"))
      (libsource (lib "Database_Libs2") (part "TEST-PAD"))
    )
    (comp (ref "SIM1")
      (value "SIMIC")
      (footprint "SIMIC")
      (description "SIMIC虚拟器件")
      (fields (field (name "PART NUMBER") "AD_XN_SIMIC_01"))
      (libsource (lib "Database_Libs2") (part "05_SIMIC"))
    )
    (comp (ref "SIM2")
      (value "SIMIC")
      (footprint "SIMIC")
      (description "SIMIC虚拟器件")
      (fields (field (name "PART NUMBER") "AD_XN_SIMIC_01"))
      (libsource (lib "Database_Libs2") (part "05_SIMIC"))
    )
    (comp (ref "TVS5")
      (value "SMAJ7.5A")
      (footprint "PCBComponent_1 - duplicate4")
      (description "SMBJ6.0CA,DO-214AA,10.3 V,6.0 V,600 W,58.3 A,800 uA,上海君耀电子有限公司,SMBJ6.0CA")
      (fields (field (name "PART NUMBER") "101040101-0024"))
      (libsource (lib "Database_Libs2") (part "05_SMBJ6.0CA"))
    )
    (comp (ref "U8")
      (value "M5310-E")
      (footprint "M5310-E")
      (description "M5310-E MBRH0S00,/,电信、移动NB-IoT,19mm*18.4mm*2.2mm，LCC+LGA贴片式封装,B5,B8,BLE 5.0,中移物联网有限公司")
      (fields (field (name "PART NUMBER") "1011402-0235"))
      (libsource (lib "Database_Libs2") (part "01_M5310-E"))
    )
    (comp (ref "U10")
      (value "JW5031S")
      (footprint "PCBComponent_1 - duplicate1")
      (libsource (lib "Schlib1") (part "Component_3"))
    )
    (comp (ref "U11")
      (value "SP485EEN")
      (footprint "SOP8")
      (description "SP485EEN,SOP8")
      (fields (field (name "PART NUMBER") "101050101-0065"))
      (libsource (lib "Database_Libs1") (part "SP485EEN"))
    )
    (comp (ref "U13")
      (value "DB809")
      (footprint "DB809")
      (description "北高智蓝牙模块DB809")
      (fields (field (name "PART NUMBER") "1011402-0194") (field (name "SMD/DIP") "SMD"))
      (libsource (lib "Database_Libs2") (part "01_DB809"))
    )
    (comp (ref "U14")
      (value "07_HP303B")
      (footprint "HP303B")
      (description "HP303B,4.7mm*3.7mm,惠贻华普,HP303B,含铅")
      (fields (field (name "PART NUMBER") "1011301-0022"))
      (libsource (lib "Database_Libs2") (part "07_HP303B"))
    )
    (comp (ref "U16") (value "4052") (footprint "SIM卡转换开关") (libsource (lib "*") (part "Pro87.tmp_4052_23")))
    (comp (ref "U20")
      (value "GM6250-5.0ST89RG")
      (footprint "SOT-89")
      (description "GM6250-5.0ST89RG,GM6250-5.0ST89RG,SOT-89,12 V,0 V,0 V,5 V,250mA,1.0 uA,美国GAMMA")
      (fields (field (name "PART NUMBER") "1010503-0021"))
      (libsource (lib "Database_Libs2") (part "02_GM6250-5.0ST89RG"))
    )
    (comp (ref "W1")
      (value "ANT-IPEX")
      (footprint "ANT-IPEX_1")
      (description "UB06000058A,3*3.1*1.25mm,公头,单排,IPEX一代板端")
      (fields (field (name "PART NUMBER") "1010902-0145"))
      (libsource (lib "Database_Libs2") (part "天线"))
    )
  )
  (nets
    (net (code "1") (name "/485A") (class "Default")
      (node (ref "D21") (pin "2") (pinfunction "K_2") (pintype "passive"))
      (node (ref "D3") (pin "1") (pinfunction "A_1") (pintype "passive"))
      (node (ref "P10") (pin "4") (pinfunction "GND_4") (pintype "passive"))
      (node (ref "R111") (pin "2") (pinfunction "2_2") (pintype "passive"))
      (node (ref "U11") (pin "6") (pinfunction "A_6") (pintype "passive"))
    )
    (net (code "2") (name "/485B") (class "Default")
      (node (ref "D2") (pin "1") (pinfunction "A_1") (pintype "passive"))
      (node (ref "D3") (pin "2") (pinfunction "K_2") (pintype "passive"))
      (node (ref "P10") (pin "5") (pinfunction "GND_5") (pintype "passive"))
      (node (ref "R61") (pin "1") (pinfunction "1_1") (pintype "passive"))
      (node (ref "U11") (pin "7") (pinfunction "B_7") (pintype "passive"))
    )
    (net (code "3") (name "/BLE_RXD1") (class "Default")
      (node (ref "U13") (pin "9") (pinfunction "P0.14_9") (pintype "passive"))
    )
    (net (code "4") (name "/BLE_TXD1") (class "Default")
      (node (ref "U13") (pin "8") (pinfunction "P0.12_8") (pintype "passive"))
    )
    (net (code "5") (name "/CARD_BSL") (class "Default")
      (node (ref "BSL1") (pin "1") (pinfunction "1_1") (pintype "passive"))
      (node (ref "C29") (pin "2") (pinfunction "2_2") (pintype "passive"))
      (node (ref "C95") (pin "1") (pinfunction "1_1") (pintype "passive"))
      (node (ref "J4") (pin "1") (pinfunction "XB_1") (pintype "passive"))
      (node (ref "R55") (pin "1") (pinfunction "1_1") (pintype "passive"))
    )
    (net (code "6") (name "/CARD_POW") (class "Default")
      (node (ref "C96") (pin "2") (pinfunction "2_2") (pintype "passive"))
      (node (ref "CPOW1") (pin "1") (pinfunction "1_1") (pintype "passive"))
      (node (ref "J4") (pin "6") (pinfunction "VCC_6") (pintype "passive"))
      (node (ref "R51") (pin "1") (pinfunction "1_1") (pintype "passive"))
    )
    (net (code "7") (name "/CARD_POW_EN") (class "Default")
      (node (ref "D18") (pin "2") (pinfunction "2_2") (pintype "passive"))
    )
    (net (code "8") (name "/CARD_RST") (class "Default")
      (node (ref "C100") (pin "1") (pinfunction "1_1") (pintype "passive"))
      (node (ref "J4") (pin "4") (pinfunction "RST_4") (pintype "passive"))
      (node (ref "R75") (pin "2") (pinfunction "2_2") (pintype "passive"))
      (node (ref "RST1") (pin "1") (pinfunction "1_1") (pintype "passive"))
    )
    (net (code "9") (name "/CARD_SCLK") (class "Default")
      (node (ref "C99") (pin "1") (pinfunction "1_1") (pintype "passive"))
      (node (ref "J4") (pin "3") (pinfunction "CLK_3") (pintype "passive"))
      (node (ref "R53") (pin "2") (pinfunction "2_2") (pintype "passive"))
      (node (ref "SCLK1") (pin "1") (pinfunction "1_1") (pintype "passive"))
    )
    (net (code "10") (name "/CARD_SDA") (class "Default")
      (node (ref "C98") (pin "1") (pinfunction "1_1") (pintype "passive"))
      (node (ref "DATA1") (pin "1") (pinfunction "1_1") (pintype "passive"))
      (node (ref "J4") (pin "2") (pinfunction "I/O_2") (pintype "passive"))
      (node (ref "R54") (pin "2") (pinfunction "2_2") (pintype "passive"))
    )
    (net (code "11") (name "/D_RXD") (class "Default")
      (node (ref "P8") (pin "2") (pinfunction "2_2") (pintype "passive"))
      (node (ref "U8") (pin "19") (pinfunction "DBG_RXD_19") (pintype "passive"))
    )
    (net (code "12") (name "/D_TXD") (class "Default")
      (node (ref "P8") (pin "3") (pinfunction "3_3") (pintype "passive"))
      (node (ref "U8") (pin "18") (pinfunction "DBG_TXD_18") (pintype "passive"))
    )
    (net (code "13") (name "/HP303_CTRL") (class "Default")
      (node (ref "R21") (pin "1") (pinfunction "1_1") (pintype "passive"))
    )
    (net (code "14") (name "/HP303_SCL") (class "Default")
      (node (ref "R12") (pin "2") (pinfunction "2_2") (pintype "passive"))
      (node (ref "U14") (pin "5") (pinfunction "SCL_5") (pintype "passive"))
    )
    (net (code "15") (name "/HP303_SDA") (class "Default")
      (node (ref "R13") (pin "2") (pinfunction "2_2") (pintype "passive"))
      (node (ref "U14") (pin "6") (pinfunction "SDA_6") (pintype "passive"))
    )
    (net (code "16") (name "/HP303_VCC") (class "Default")
      (node (ref "C12") (pin "1") (pinfunction "1_1") (pintype "passive"))
      (node (ref "Q2") (pin "3") (pinfunction "D_3") (pintype "passive"))
      (node (ref "R1") (pin "2") (pinfunction "2_2") (pintype "passive"))
      (node (ref "R12") (pin "1") (pinfunction "1_1") (pintype "passive"))
      (node (ref "R13") (pin "1") (pinfunction "1_1") (pintype "passive"))
      (node (ref "U14") (pin "1") (pinfunction "VDDIO_1") (pintype "passive"))
      (node (ref "U14") (pin "3") (pinfunction "VDD_3") (pintype "passive"))
    )
    (net (code "17") (name "/MAIN_ANT") (class "Default")
      (node (ref "C1") (pin "1") (pinfunction "1_1") (pintype "passive"))
      (node (ref "R2") (pin "2") (pinfunction "2_2") (pintype "passive"))
      (node (ref "U8") (pin "28") (pinfunction "RF_ANT_28") (pintype "passive"))
    )
    (net (code "18") (name "/NB_POWER") (class "Default")
      (node (ref "R88") (pin "2") (pinfunction "2_2") (pintype "passive"))
    )
    (net (code "19") (name "/NB_PWRKEY") (class "Default")
      (node (ref "R95") (pin "1") (pinfunction "1_1") (pintype "passive"))
    )
    (net (code "20") (name "/NB_RST") (class "Default")
      (node (ref "R68") (pin "2") (pinfunction "2_2") (pintype "passive"))
    )
    (net (code "21") (name "/NB_RxD4") (class "Default")
      (node (ref "R91") (pin "2") (pinfunction "2_2") (pintype "passive"))
    )
    (net (code "22") (name "/NB_TxD4") (class "Default")
      (node (ref "D8") (pin "3") (pinfunction "C_3") (pintype "passive"))
      (node (ref "R92") (pin "2") (pinfunction "2_2") (pintype "passive"))
    )
    (net (code "23") (name "/RESET") (class "Default")
      (node (ref "Q15") (pin "3") (pinfunction "C_3") (pintype "passive"))
      (node (ref "U8") (pin "15") (pinfunction "RESET_15") (pintype "passive"))
    )
    (net (code "24") (name "/RS485_RXD") (class "Default")
      (node (ref "Q21") (pin "4") (pintype "passive"))
      (node (ref "R64") (pin "1") (pinfunction "1_1") (pintype "passive"))
    )
    (net (code "25") (name "/RS485_TXD") (class "Default") (node (ref "Q20") (pin "2") (pintype "passive")))
    (net (code "26") (name "/SIM_CLK1") (class "Default")
      (node (ref "R11") (pin "1") (pinfunction "1_1") (pintype "passive"))
      (node (ref "SIM1") (pin "6") (pinfunction "CLK_6") (pintype "passive"))
      (node (ref "U16") (pin "12") (pinfunction "X0_12") (pintype "passive"))
    )
    (net (code "27") (name "/SIM_CLK2") (class "Default")
      (node (ref "SIM2") (pin "6") (pinfunction "CLK_6") (pintype "passive"))
      (node (ref "U16") (pin "14") (pinfunction "X1_14") (pintype "passive"))
    )
    (net (code "28") (name "/SIM_DATA1") (class "Default")
      (node (ref "R10") (pin "2") (pinfunction "2_2") (pintype "passive"))
      (node (ref "SIM1") (pin "2") (pinfunction "I/O_2") (pintype "passive"))
      (node (ref "SIM1") (pin "3") (pinfunction "I/O_3") (pintype "passive"))
      (node (ref "U16") (pin "1") (pinfunction "Y0_1") (pintype "passive"))
    )
    (net (code "29") (name "/SIM_DATA2") (class "Default")
      (node (ref "SIM2") (pin "2") (pinfunction "I/O_2") (pintype "passive"))
      (node (ref "SIM2") (pin "3") (pinfunction "I/O_3") (pintype "passive"))
      (node (ref "U16") (pin "5") (pinfunction "Y1_5") (pintype "passive"))
    )
    (net (code "30") (name "/SIM_RST") (class "Default")
      (node (ref "C58") (pin "1") (pinfunction "1_1") (pintype "passive"))
      (node (ref "R6") (pin "2") (pinfunction "2_2") (pintype "passive"))
      (node (ref "SIM1") (pin "7") (pinfunction "RST_7") (pintype "passive"))
      (node (ref "SIM2") (pin "7") (pinfunction "RST_7") (pintype "passive"))
    )
    (net (code "31") (name "/STATE_BLE") (class "Default")
      (node (ref "U13") (pin "10") (pinfunction "P0.05/AIN3_10") (pintype "passive"))
    )
    (net (code "32") (name "/USIM_CLK") (class "Default")
      (node (ref "R5") (pin "1") (pinfunction "1_1") (pintype "passive"))
      (node (ref "U8") (pin "12") (pinfunction "SIM_CLK_12") (pintype "passive"))
    )
    (net (code "33") (name "/USIM_DATA") (class "Default")
      (node (ref "R4") (pin "1") (pinfunction "1_1") (pintype "passive"))
      (node (ref "R52") (pin "1") (pinfunction "1_1") (pintype "passive"))
      (node (ref "U8") (pin "10") (pinfunction "SIM_DATA_10") (pintype "passive"))
    )
    (net (code "34") (name "/USIM_RST") (class "Default")
      (node (ref "R6") (pin "1") (pinfunction "1_1") (pintype "passive"))
      (node (ref "U8") (pin "13") (pinfunction "SIM_RST_13") (pintype "passive"))
    )
    (net (code "35") (name "/USIM_XCLK") (class "Default")
      (node (ref "C57") (pin "1") (pinfunction "1_1") (pintype "passive"))
      (node (ref "R11") (pin "2") (pinfunction "2_2") (pintype "passive"))
      (node (ref "R5") (pin "2") (pinfunction "2_2") (pintype "passive"))
      (node (ref "U16") (pin "13") (pinfunction "X_13") (pintype "passive"))
    )
    (net (code "36") (name "/USIM_YDATA") (class "Default")
      (node (ref "C59") (pin "1") (pinfunction "1_1") (pintype "passive"))
      (node (ref "R10") (pin "1") (pinfunction "1_1") (pintype "passive"))
      (node (ref "R4") (pin "2") (pinfunction "2_2") (pintype "passive"))
      (node (ref "U16") (pin "3") (pinfunction "Y_3") (pintype "passive"))
    )
    (net (code "37") (name "/VDD_BLE_CTL") (class "Default")
      (node (ref "R31") (pin "1") (pinfunction "1_1") (pintype "passive"))
    )
    (net (code "38") (name "5V") (class "Default")
      (node (ref "D22") (pin "2") (pinfunction "2_2") (pintype "passive"))
    )
    (net (code "39") (name "485_5V") (class "Default")
      (node (ref "C47") (pin "2") (pinfunction "2_2") (pintype "passive"))
      (node (ref "D25") (pin "2") (pinfunction "2_2") (pintype "passive"))
      (node (ref "R111") (pin "1") (pinfunction "1_1") (pintype "passive"))
      (node (ref "R113") (pin "1") (pinfunction "1_1") (pintype "passive"))
      (node (ref "R63") (pin "1") (pinfunction "1_1") (pintype "passive"))
      (node (ref "R77") (pin "2") (pinfunction "2_2") (pintype "passive"))
      (node (ref "U11") (pin "8") (pinfunction "VCC_8") (pintype "passive"))
    )
    (net (code "40") (name "485_GND") (class "Default")
      (node (ref "C47") (pin "1") (pinfunction "1_1") (pintype "passive"))
      (node (ref "C97") (pin "2") (pinfunction "2_2") (pintype "passive"))
      (node (ref "D2") (pin "2") (pinfunction "K_2") (pintype "passive"))
      (node (ref "D21") (pin "1") (pinfunction "A_1") (pintype "passive"))
      (node (ref "P10") (pin "6") (pinfunction "GND_6") (pintype "passive"))
      (node (ref "Q20") (pin "3") (pintype "passive"))
      (node (ref "Q21") (pin "3") (pintype "passive"))
      (node (ref "Q24") (pin "2") (pinfunction "E_2") (pintype "passive"))
      (node (ref "R61") (pin "2") (pinfunction "2_2") (pintype "passive"))
      (node (ref "TVS5") (pin "1") (pinfunction "1_1") (pintype "passive"))
      (node (ref "U11") (pin "5") (pinfunction "GND_5") (pintype "passive"))
      (node (ref "U20") (pin "1") (pinfunction "GND_1") (pintype "passive"))
    )
    (net (code "41") (name "GND") (class "Default")
      (node (ref "C1") (pin "2") (pinfunction "2_2") (pintype "passive"))
      (node (ref "C100") (pin "2") (pinfunction "2_2") (pintype "passive"))
      (node (ref "C12") (pin "2") (pinfunction "2_2") (pintype "passive"))
      (node (ref "C2") (pin "2") (pinfunction "2_2") (pintype "passive"))
      (node (ref "C29") (pin "1") (pinfunction "1_1") (pintype "passive"))
      (node (ref "C3") (pin "1") (pinfunction "1_1") (pintype "passive"))
      (node (ref "C34") (pin "2") (pinfunction "2_2") (pintype "passive"))
      (node (ref "C40") (pin "2") (pinfunction "2_2") (pintype "passive"))
      (node (ref "C42") (pin "2") (pinfunction "2_2") (pintype "passive"))
      (node (ref "C43") (pin "1") (pinfunction "1_1") (pintype "passive"))
      (node (ref "C44") (pin "2") (pinfunction "2_2") (pintype "passive"))
      (node (ref "C45") (pin "2") (pinfunction "2_2") (pintype "passive"))
      (node (ref "C57") (pin "2") (pinfunction "2_2") (pintype "passive"))
      (node (ref "C58") (pin "2") (pinfunction "2_2") (pintype "passive"))
      (node (ref "C59") (pin "2") (pinfunction "2_2") (pintype "passive"))
      (node (ref "C63") (pin "2") (pinfunction "2_2") (pintype "passive"))
      (node (ref "C65") (pin "2") (pinfunction "2_2") (pintype "passive"))
      (node (ref "C75") (pin "2") (pinfunction "2_2") (pintype "passive"))
      (node (ref "C76") (pin "2") (pinfunction "2_2") (pintype "passive"))
      (node (ref "C8") (pin "2") (pinfunction "2_2") (pintype "passive"))
      (node (ref "C95") (pin "2") (pinfunction "2_2") (pintype "passive"))
      (node (ref "C96") (pin "1") (pinfunction "1_1") (pintype "passive"))
      (node (ref "C98") (pin "2") (pinfunction "2_2") (pintype "passive"))
      (node (ref "C99") (pin "2") (pinfunction "2_2") (pintype "passive"))
      (node (ref "J4") (pin "5") (pinfunction "GND_5") (pintype "passive"))
      (node (ref "P10") (pin "2") (pinfunction "UD-_2") (pintype "passive"))
      (node (ref "P8") (pin "1") (pinfunction "1_1") (pintype "passive"))
      (node (ref "Q15") (pin "2") (pinfunction "E_2") (pintype "passive"))
      (node (ref "Q16") (pin "2") (pinfunction "E_2") (pintype "passive"))
      (node (ref "Q19") (pin "2") (pinfunction "E_2") (pintype "passive"))
      (node (ref "R115") (pin "1") (pinfunction "1_1") (pintype "passive"))
      (node (ref "R32") (pin "2") (pinfunction "2_2") (pintype "passive"))
      (node (ref "R71") (pin "2") (pinfunction "2_2") (pintype "passive"))
      (node (ref "R8") (pin "1") (pinfunction "1_1") (pintype "passive"))
      (node (ref "R94") (pin "2") (pinfunction "2_2") (pintype "passive"))
      (node (ref "R96") (pin "2") (pinfunction "2_2") (pintype "passive"))
      (node (ref "U10") (pin "1") (pinfunction "GND_1") (pintype "passive"))
      (node (ref "U13") (pin "1") (pinfunction "GND_1") (pintype "passive"))
      (node (ref "U13") (pin "15") (pinfunction "GND_15") (pintype "passive"))
      (node (ref "U14") (pin "2") (pinfunction "GND_2") (pintype "passive"))
      (node (ref "U16") (pin "7") (pinfunction "VEE_7") (pintype "passive"))
      (node (ref "U16") (pin "8") (pinfunction "GND_8") (pintype "power_in"))
      (node (ref "U8") (pin "26") (pinfunction "GND_26") (pintype "passive"))
      (node (ref "U8") (pin "27") (pinfunction "GND_27") (pintype "passive"))
      (node (ref "U8") (pin "29") (pinfunction "GND_29") (pintype "passive"))
      (node (ref "U8") (pin "30") (pinfunction "GND_30") (pintype "passive"))
      (node (ref "U8") (pin "42") (pinfunction "GND_42") (pintype "passive"))
      (node (ref "U8") (pin "43") (pinfunction "GND_43") (pintype "passive"))
      (node (ref "U8") (pin "45") (pinfunction "GND_45") (pintype "passive"))
      (node (ref "U8") (pin "46") (pinfunction "GND_46") (pintype "passive"))
      (node (ref "U8") (pin "48") (pinfunction "GND_48") (pintype "passive"))
      (node (ref "U8") (pin "49") (pinfunction "GND_49") (pintype "passive"))
      (node (ref "U8") (pin "50") (pinfunction "GND_50") (pintype "passive"))
      (node (ref "U8") (pin "54") (pinfunction "GND_54") (pintype "passive"))
      (node (ref "U8") (pin "56") (pinfunction "GND_56") (pintype "passive"))
      (node (ref "U8") (pin "58") (pinfunction "GND_58") (pintype "passive"))
      (node (ref "U8") (pin "62") (pinfunction "GND_62") (pintype "passive"))
      (node (ref "U8") (pin "64") (pinfunction "GND_64") (pintype "passive"))
      (node (ref "U8") (pin "66") (pinfunction "GND_66") (pintype "passive"))
      (node (ref "W1") (pin "2") (pinfunction "GND_2") (pintype "passive"))
    )
    (net (code "42") (name "NB_VIN1") (class "Default")
      (node (ref "C75") (pin "1") (pinfunction "1_1") (pintype "passive"))
      (node (ref "C76") (pin "1") (pinfunction "1_1") (pintype "passive"))
      (node (ref "Q23") (pin "3") (pinfunction "D_3") (pintype "passive"))
      (node (ref "R102") (pin "1") (pinfunction "1_1") (pintype "passive"))
      (node (ref "U10") (pin "3") (pinfunction "VIN_3") (pintype "passive"))
    )
    (net (code "43") (name "Net-(D18-Pad1)") (class "Default")
      (node (ref "D18") (pin "1") (pinfunction "1_1") (pintype "passive"))
      (node (ref "R44") (pin "1") (pinfunction "1_1") (pintype "passive"))
    )
    (net (code "44") (name "Net-(P10-UD+)") (class "Default")
      (node (ref "C97") (pin "1") (pinfunction "1_1") (pintype "passive"))
      (node (ref "P10") (pin "3") (pinfunction "UD+_3") (pintype "passive"))
      (node (ref "TVS5") (pin "2") (pinfunction "2_2") (pintype "passive"))
      (node (ref "U20") (pin "2") (pinfunction "Vin_2") (pintype "passive"))
    )
    (net (code "45") (name "Net-(P10-VCC)") (class "Default")
      (node (ref "D22") (pin "1") (pinfunction "1_1") (pintype "passive"))
      (node (ref "P10") (pin "1") (pinfunction "VCC_1") (pintype "passive"))
    )
    (net (code "46") (name "Net-(Q2-G)") (class "Default")
      (node (ref "Q2") (pin "1") (pinfunction "G_1") (pintype "passive"))
      (node (ref "R14") (pin "2") (pinfunction "2_2") (pintype "passive"))
      (node (ref "R21") (pin "2") (pinfunction "2_2") (pintype "passive"))
    )
    (net (code "47") (name "Net-(Q8-G)") (class "Default")
      (node (ref "Q8") (pin "1") (pinfunction "G_1") (pintype "passive"))
      (node (ref "R31") (pin "2") (pinfunction "2_2") (pintype "passive"))
      (node (ref "R35") (pin "2") (pinfunction "2_2") (pintype "passive"))
    )
    (net (code "48") (name "Net-(Q15-B)") (class "Default")
      (node (ref "Q15") (pin "1") (pinfunction "B_1") (pintype "passive"))
      (node (ref "R68") (pin "1") (pinfunction "1_1") (pintype "passive"))
      (node (ref "R71") (pin "1") (pinfunction "1_1") (pintype "passive"))
    )
    (net (code "49") (name "Net-(Q16-B)") (class "Default")
      (node (ref "Q16") (pin "1") (pinfunction "B_1") (pintype "passive"))
      (node (ref "R88") (pin "1") (pinfunction "1_1") (pintype "passive"))
    )
    (net (code "50") (name "Net-(Q16-C)") (class "Default")
      (node (ref "Q16") (pin "3") (pinfunction "C_3") (pintype "passive"))
      (node (ref "R86") (pin "1") (pinfunction "1_1") (pintype "passive"))
    )
    (net (code "51") (name "Net-(Q17-B)") (class "Default")
      (node (ref "Q17") (pin "1") (pinfunction "B_1") (pintype "passive"))
      (node (ref "R44") (pin "2") (pinfunction "2_2") (pintype "passive"))
    )
    (net (code "52") (name "Net-(Q17-C)") (class "Default")
      (node (ref "Q17") (pin "3") (pinfunction "C_3") (pintype "passive"))
      (node (ref "R51") (pin "2") (pinfunction "2_2") (pintype "passive"))
      (node (ref "R53") (pin "1") (pinfunction "1_1") (pintype "passive"))
      (node (ref "R54") (pin "1") (pinfunction "1_1") (pintype "passive"))
      (node (ref "R75") (pin "1") (pinfunction "1_1") (pintype "passive"))
    )
    (net (code "53") (name "Net-(Q19-B)") (class "Default")
      (node (ref "Q19") (pin "1") (pinfunction "B_1") (pintype "passive"))
      (node (ref "R95") (pin "2") (pinfunction "2_2") (pintype "passive"))
      (node (ref "R96") (pin "1") (pinfunction "1_1") (pintype "passive"))
    )
    (net (code "54") (name "Net-(Q19-C)") (class "Default")
      (node (ref "Q19") (pin "3") (pinfunction "C_3") (pintype "passive"))
      (node (ref "R93") (pin "1") (pinfunction "1_1") (pintype "passive"))
      (node (ref "U16") (pin "10") (pinfunction "A_10") (pintype "input"))
    )
    (net (code "55") (name "Net-(Q20-Pad1)") (class "Default")
      (node (ref "Q20") (pin "1") (pintype "passive"))
      (node (ref "R112") (pin "2") (pinfunction "2_2") (pintype "passive"))
    )
    (net (code "56") (name "Net-(Q21-Pad1)") (class "Default")
      (node (ref "Q21") (pin "1") (pintype "passive"))
      (node (ref "R77") (pin "1") (pinfunction "1_1") (pintype "passive"))
    )
    (net (code "57") (name "Net-(Q23-G)") (class "Default")
      (node (ref "Q23") (pin "1") (pinfunction "G_1") (pintype "passive"))
      (node (ref "R85") (pin "2") (pinfunction "2_2") (pintype "passive"))
      (node (ref "R86") (pin "2") (pinfunction "2_2") (pintype "passive"))
    )
    (net (code "58") (name "Net-(Q24-B)") (class "Default")
      (node (ref "Q24") (pin "1") (pinfunction "B_1") (pintype "passive"))
      (node (ref "R65") (pin "1") (pinfunction "1_1") (pintype "passive"))
    )
    (net (code "59") (name "Net-(Q24-C)") (class "Default")
      (node (ref "Q24") (pin "3") (pinfunction "C_3") (pintype "passive"))
      (node (ref "R63") (pin "2") (pinfunction "2_2") (pintype "passive"))
      (node (ref "U11") (pin "2") (pinfunction "~{RE}_2") (pintype "passive"))
      (node (ref "U11") (pin "3") (pinfunction "DE_3") (pintype "passive"))
    )
    (net (code "60") (name "Net-(U8-UART_RX0)") (class "Default")
      (node (ref "D8") (pin "1") (pinfunction "A_1") (pintype "passive"))
      (node (ref "D8") (pin "2") (pinfunction "A_2") (pintype "passive"))
      (node (ref "R7") (pin "1") (pinfunction "1_1") (pintype "passive"))
      (node (ref "R92") (pin "1") (pinfunction "1_1") (pintype "passive"))
      (node (ref "U8") (pin "2") (pinfunction "UART_RX0_2") (pintype "passive"))
    )
    (net (code "61") (name "Net-(U8-UART_TX0)") (class "Default")
      (node (ref "R91") (pin "1") (pinfunction "1_1") (pintype "passive"))
      (node (ref "U8") (pin "1") (pinfunction "UART_TX0_1") (pintype "passive"))
    )
    (net (code "62") (name "Net-(U10-BST)") (class "Default")
      (node (ref "C24") (pin "2") (pinfunction "2_2") (pintype "passive"))
      (node (ref "U10") (pin "6") (pinfunction "BST_6") (pintype "passive"))
    )
    (net (code "63") (name "Net-(U10-EN)") (class "Default")
      (node (ref "R102") (pin "2") (pinfunction "2_2") (pintype "passive"))
      (node (ref "U10") (pin "5") (pinfunction "EN_5") (pintype "passive"))
    )
    (net (code "64") (name "Net-(U10-FB)") (class "Default")
      (node (ref "R114") (pin "2") (pinfunction "2_2") (pintype "passive"))
      (node (ref "R115") (pin "2") (pinfunction "2_2") (pintype "passive"))
      (node (ref "U10") (pin "4") (pinfunction "FB_4") (pintype "passive"))
    )
    (net (code "65") (name "Net-(U10-SW)") (class "Default")
      (node (ref "C24") (pin "1") (pinfunction "1_1") (pintype "passive"))
      (node (ref "L1") (pin "1") (pinfunction "1_1") (pintype "passive"))
      (node (ref "U10") (pin "2") (pinfunction "SW_2") (pintype "passive"))
    )
    (net (code "66") (name "Net-(U11-DI)") (class "Default")
      (node (ref "Q20") (pin "4") (pintype "passive"))
      (node (ref "R113") (pin "2") (pinfunction "2_2") (pintype "passive"))
      (node (ref "R65") (pin "2") (pinfunction "2_2") (pintype "passive"))
      (node (ref "U11") (pin "4") (pinfunction "DI_4") (pintype "passive"))
    )
    (net (code "67") (name "Net-(U11-RO)") (class "Default")
      (node (ref "Q21") (pin "2") (pintype "passive"))
      (node (ref "U11") (pin "1") (pinfunction "RO_1") (pintype "passive"))
    )
    (net (code "68") (name "Net-(U14-SDO)") (class "Default")
      (node (ref "R1") (pin "1") (pinfunction "1_1") (pintype "passive"))
      (node (ref "R32") (pin "1") (pinfunction "1_1") (pintype "passive"))
      (node (ref "U14") (pin "8") (pinfunction "SDO_8") (pintype "passive"))
    )
    (net (code "69") (name "Net-(U16-B)") (class "Default")
      (node (ref "R8") (pin "2") (pinfunction "2_2") (pintype "passive"))
      (node (ref "U16") (pin "9") (pinfunction "B_9") (pintype "input"))
    )
    (net (code "70") (name "Net-(U16-INH)") (class "Default")
      (node (ref "R94") (pin "1") (pinfunction "1_1") (pintype "passive"))
      (node (ref "U16") (pin "6") (pinfunction "INH_6") (pintype "input"))
    )
    (net (code "71") (name "Net-(U20-Vout)") (class "Default")
      (node (ref "D25") (pin "1") (pinfunction "1_1") (pintype "passive"))
      (node (ref "U20") (pin "3") (pinfunction "Vout_3") (pintype "passive"))
    )
    (net (code "72") (name "Net-(W1-ANT)") (class "Default")
      (node (ref "C2") (pin "1") (pinfunction "1_1") (pintype "passive"))
      (node (ref "R2") (pin "1") (pinfunction "1_1") (pintype "passive"))
      (node (ref "W1") (pin "1") (pinfunction "ANT_1") (pintype "passive"))
    )
    (net (code "73") (name "USIM_GND") (class "Default")
      (node (ref "C4") (pin "2") (pinfunction "2_2") (pintype "passive"))
      (node (ref "C5") (pin "2") (pinfunction "2_2") (pintype "passive"))
      (node (ref "C56") (pin "2") (pinfunction "2_2") (pintype "passive"))
      (node (ref "C62") (pin "2") (pinfunction "2_2") (pintype "passive"))
      (node (ref "SIM1") (pin "1") (pinfunction "VSS_1") (pintype "passive"))
      (node (ref "SIM2") (pin "1") (pinfunction "VSS_1") (pintype "passive"))
      (node (ref "U8") (pin "8") (pinfunction "SIM_GND_8") (pintype "passive"))
    )
    (net (code "74") (name "USIM_VDD") (class "Default")
      (node (ref "C4") (pin "1") (pinfunction "1_1") (pintype "passive"))
      (node (ref "C5") (pin "1") (pinfunction "1_1") (pintype "passive"))
      (node (ref "C56") (pin "1") (pinfunction "1_1") (pintype "passive"))
      (node (ref "C62") (pin "1") (pinfunction "1_1") (pintype "passive"))
      (node (ref "R52") (pin "2") (pinfunction "2_2") (pintype "passive"))
      (node (ref "SIM1") (pin "8") (pinfunction "VDD_8") (pintype "passive"))
      (node (ref "SIM2") (pin "8") (pinfunction "VDD_8") (pintype "passive"))
      (node (ref "U8") (pin "11") (pinfunction "SIM_VDD_11") (pintype "passive"))
    )
    (net (code "75") (name "VCC") (class "Default")
      (node (ref "Q17") (pin "2") (pinfunction "E_2") (pintype "passive"))
      (node (ref "Q2") (pin "2") (pinfunction "S_2") (pintype "passive"))
      (node (ref "Q8") (pin "2") (pinfunction "S_2") (pintype "passive"))
      (node (ref "R112") (pin "1") (pinfunction "1_1") (pintype "passive"))
      (node (ref "R14") (pin "1") (pinfunction "1_1") (pintype "passive"))
      (node (ref "R35") (pin "1") (pinfunction "1_1") (pintype "passive"))
      (node (ref "R55") (pin "2") (pinfunction "2_2") (pintype "passive"))
      (node (ref "R64") (pin "2") (pinfunction "2_2") (pintype "passive"))
    )
    (net (code "76") (name "VDD") (class "Default")
      (node (ref "C3") (pin "2") (pinfunction "2_2") (pintype "passive"))
      (node (ref "C34") (pin "1") (pinfunction "1_1") (pintype "passive"))
      (node (ref "C40") (pin "1") (pinfunction "1_1") (pintype "passive"))
      (node (ref "C42") (pin "1") (pinfunction "1_1") (pintype "passive"))
      (node (ref "C43") (pin "2") (pinfunction "2_2") (pintype "passive"))
      (node (ref "C44") (pin "1") (pinfunction "1_1") (pintype "passive"))
      (node (ref "C45") (pin "1") (pinfunction "1_1") (pintype "passive"))
      (node (ref "L1") (pin "2") (pinfunction "2_2") (pintype "passive"))
      (node (ref "R114") (pin "1") (pinfunction "1_1") (pintype "passive"))
      (node (ref "R93") (pin "2") (pinfunction "2_2") (pintype "passive"))
      (node (ref "U16") (pin "16") (pinfunction "VCC_16") (pintype "power_in"))
      (node (ref "U8") (pin "24") (pinfunction "VBAT_24") (pintype "passive"))
      (node (ref "U8") (pin "25") (pinfunction "VBAT_25") (pintype "passive"))
    )
    (net (code "77") (name "VDD_BLE") (class "Default")
      (node (ref "C63") (pin "1") (pinfunction "1_1") (pintype "passive"))
      (node (ref "C65") (pin "1") (pinfunction "1_1") (pintype "passive"))
      (node (ref "Q8") (pin "3") (pinfunction "D_3") (pintype "passive"))
      (node (ref "U13") (pin "14") (pinfunction "VDD_14") (pintype "passive"))
    )
    (net (code "78") (name "VDD_EXT") (class "Default")
      (node (ref "C8") (pin "1") (pinfunction "1_1") (pintype "passive"))
      (node (ref "R7") (pin "2") (pinfunction "2_2") (pintype "passive"))
      (node (ref "U8") (pin "16") (pinfunction "VDD_EXT_16") (pintype "passive"))
    )
    (net (code "79") (name "VIN_NB") (class "Default")
      (node (ref "Q23") (pin "2") (pinfunction "S_2") (pintype "passive"))
      (node (ref "R85") (pin "1") (pinfunction "1_1") (pintype "passive"))
    )
    (net (code "80") (name "unconnected-(SIM1-NC-Pad4)") (class "Default")
      (node (ref "SIM1") (pin "4") (pinfunction "NC_4") (pintype "passive"))
    )
    (net (code "81") (name "unconnected-(SIM1-NC-Pad5)") (class "Default")
      (node (ref "SIM1") (pin "5") (pinfunction "NC_5") (pintype "passive"))
    )
    (net (code "82") (name "unconnected-(SIM2-NC-Pad4)") (class "Default")
      (node (ref "SIM2") (pin "4") (pinfunction "NC_4") (pintype "passive"))
    )
    (net (code "83") (name "unconnected-(SIM2-NC-Pad5)") (class "Default")
      (node (ref "SIM2") (pin "5") (pinfunction "NC_5") (pintype "passive"))
    )
    (net (code "84") (name "unconnected-(U8-32KSEL-Pad60)") (class "Default")
      (node (ref "U8") (pin "60") (pinfunction "32KSEL_60") (pintype "passive"))
    )
    (net (code "85") (name "unconnected-(U8-ADC0-Pad5)") (class "Default")
      (node (ref "U8") (pin "5") (pinfunction "ADC0_5") (pintype "passive"))
    )
    (net (code "86") (name "unconnected-(U8-ADC1-Pad6)") (class "Default")
      (node (ref "U8") (pin "6") (pinfunction "ADC1_6") (pintype "passive"))
    )
    (net (code "87") (name "unconnected-(U8-ADC2-Pad7)") (class "Default")
      (node (ref "U8") (pin "7") (pinfunction "ADC2_7") (pintype "passive"))
    )
    (net (code "88") (name "unconnected-(U8-ADC3-Pad55)") (class "Default")
      (node (ref "U8") (pin "55") (pinfunction "ADC3_55") (pintype "passive"))
    )
    (net (code "89") (name "unconnected-(U8-ADC4-Pad59)") (class "Default")
      (node (ref "U8") (pin "59") (pinfunction "ADC4_59") (pintype "passive"))
    )
    (net (code "90") (name "unconnected-(U8-GNSS_ANT-Pad44)") (class "Default")
      (node (ref "U8") (pin "44") (pinfunction "GNSS_ANT_44") (pintype "passive"))
    )
    (net (code "91") (name "unconnected-(U8-GPIO-Pad51)") (class "Default")
      (node (ref "U8") (pin "51") (pinfunction "GPIO_51") (pintype "passive"))
    )
    (net (code "92") (name "unconnected-(U8-I2C0_SCL-Pad31)") (class "Default")
      (node (ref "U8") (pin "31") (pinfunction "I2C0_SCL_31") (pintype "passive"))
    )
    (net (code "93") (name "unconnected-(U8-I2C0_SDA-Pad32)") (class "Default")
      (node (ref "U8") (pin "32") (pinfunction "I2C0_SDA_32") (pintype "passive"))
    )
    (net (code "94") (name "unconnected-(U8-I2C1_SCL-Pad33)") (class "Default")
      (node (ref "U8") (pin "33") (pinfunction "I2C1_SCL_33") (pintype "passive"))
    )
    (net (code "95") (name "unconnected-(U8-I2C1_SDA-Pad34)") (class "Default")
      (node (ref "U8") (pin "34") (pinfunction "I2C1_SDA_34") (pintype "passive"))
    )
    (net (code "96") (name "unconnected-(U8-JTAG_ENABLE-Pad52)") (class "Default")
      (node (ref "U8") (pin "52") (pinfunction "JTAG_ENABLE_52") (pintype "passive"))
    )
    (net (code "97") (name "unconnected-(U8-NETLIGHT-Pad21)") (class "Default")
      (node (ref "U8") (pin "21") (pinfunction "NETLIGHT_21") (pintype "passive"))
    )
    (net (code "98") (name "unconnected-(U8-RI-Pad23)") (class "Default")
      (node (ref "U8") (pin "23") (pinfunction "RI_23") (pintype "passive"))
    )
    (net (code "99") (name "unconnected-(U8-RSV-Pad9)") (class "Default")
      (node (ref "U8") (pin "9") (pinfunction "RSV_9") (pintype "passive"))
    )
    (net (code "100") (name "unconnected-(U8-RSV-Pad14)") (class "Default")
      (node (ref "U8") (pin "14") (pinfunction "RSV_14") (pintype "passive"))
    )
    (net (code "101") (name "unconnected-(U8-RSV-Pad17)") (class "Default")
      (node (ref "U8") (pin "17") (pinfunction "RSV_17") (pintype "passive"))
    )
    (net (code "102") (name "unconnected-(U8-RSV-Pad20)") (class "Default")
      (node (ref "U8") (pin "20") (pinfunction "RSV_20") (pintype "passive"))
    )
    (net (code "103") (name "unconnected-(U8-RSV-Pad22)") (class "Default")
      (node (ref "U8") (pin "22") (pinfunction "RSV_22") (pintype "passive"))
    )
    (net (code "104") (name "unconnected-(U8-RSV-Pad41)") (class "Default")
      (node (ref "U8") (pin "41") (pinfunction "RSV_41") (pintype "passive"))
    )
    (net (code "105") (name "unconnected-(U8-SPI0_CK-Pad35)") (class "Default")
      (node (ref "U8") (pin "35") (pinfunction "SPI0_CK_35") (pintype "passive"))
    )
    (net (code "106") (name "unconnected-(U8-SPI0_CSN-Pad37)") (class "Default")
      (node (ref "U8") (pin "37") (pinfunction "SPI0_CSN_37") (pintype "passive"))
    )
    (net (code "107") (name "unconnected-(U8-SPI0_RXD-Pad36)") (class "Default")
      (node (ref "U8") (pin "36") (pinfunction "SPI0_RXD_36") (pintype "passive"))
    )
    (net (code "108") (name "unconnected-(U8-SPI0_TXD-Pad38)") (class "Default")
      (node (ref "U8") (pin "38") (pinfunction "SPI0_TXD_38") (pintype "passive"))
    )
    (net (code "109") (name "unconnected-(U8-SWD_CLK-Pad3)") (class "Default")
      (node (ref "U8") (pin "3") (pinfunction "SWD_CLK_3") (pintype "passive"))
    )
    (net (code "110") (name "unconnected-(U8-SWD_DIO-Pad4)") (class "Default")
      (node (ref "U8") (pin "4") (pinfunction "SWD_DIO_4") (pintype "passive"))
    )
    (net (code "111") (name "unconnected-(U8-UART_CTS2-Pad61)") (class "Default")
      (node (ref "U8") (pin "61") (pinfunction "UART_CTS2_61") (pintype "passive"))
    )
    (net (code "112") (name "unconnected-(U8-UART_RTS2-Pad65)") (class "Default")
      (node (ref "U8") (pin "65") (pinfunction "UART_RTS2_65") (pintype "passive"))
    )
    (net (code "113") (name "unconnected-(U8-UART_RX1-Pad40)") (class "Default")
      (node (ref "U8") (pin "40") (pinfunction "UART_RX1_40") (pintype "passive"))
    )
    (net (code "114") (name "unconnected-(U8-UART_RX2-Pad57)") (class "Default")
      (node (ref "U8") (pin "57") (pinfunction "UART_RX2_57") (pintype "passive"))
    )
    (net (code "115") (name "unconnected-(U8-UART_TX1-Pad39)") (class "Default")
      (node (ref "U8") (pin "39") (pinfunction "UART_TX1_39") (pintype "passive"))
    )
    (net (code "116") (name "unconnected-(U8-UART_TX2-Pad53)") (class "Default")
      (node (ref "U8") (pin "53") (pinfunction "UART_TX2_53") (pintype "passive"))
    )
    (net (code "117") (name "unconnected-(U8-VDD_C-Pad47)") (class "Default")
      (node (ref "U8") (pin "47") (pinfunction "VDD_C_47") (pintype "passive"))
    )
    (net (code "118") (name "unconnected-(U8-VDD_XO-Pad63)") (class "Default")
      (node (ref "U8") (pin "63") (pinfunction "VDD_XO_63") (pintype "passive"))
    )
    (net (code "119") (name "unconnected-(U13-P0.00{slash}XL1-Pad13)") (class "Default")
      (node (ref "U13") (pin "13") (pinfunction "P0.00/XL1_13") (pintype "passive"))
    )
    (net (code "120") (name "unconnected-(U13-P0.01{slash}XL2-Pad12)") (class "Default")
      (node (ref "U13") (pin "12") (pinfunction "P0.01/XL2_12") (pintype "passive"))
    )
    (net (code "121") (name "unconnected-(U13-P0.04{slash}AIN2-Pad11)") (class "Default")
      (node (ref "U13") (pin "11") (pinfunction "P0.04/AIN2_11") (pintype "passive"))
    )
    (net (code "122") (name "unconnected-(U13-P0.16-Pad7)") (class "Default")
      (node (ref "U13") (pin "7") (pinfunction "P0.16_7") (pintype "passive"))
    )
    (net (code "123") (name "unconnected-(U13-P0.18-Pad6)") (class "Default")
      (node (ref "U13") (pin "6") (pinfunction "P0.18_6") (pintype "passive"))
    )
    (net (code "124") (name "unconnected-(U13-P0.20-Pad5)") (class "Default")
      (node (ref "U13") (pin "5") (pinfunction "P0.20_5") (pintype "passive"))
    )
    (net (code "125") (name "unconnected-(U13-SWCLK-Pad3)") (class "Default")
      (node (ref "U13") (pin "3") (pinfunction "SWCLK_3") (pintype "passive"))
    )
    (net (code "126") (name "unconnected-(U13-SWDIO-Pad2)") (class "Default")
      (node (ref "U13") (pin "2") (pinfunction "SWDIO_2") (pintype "passive"))
    )
    (net (code "127") (name "unconnected-(U13-nRESET-Pad4)") (class "Default")
      (node (ref "U13") (pin "4") (pinfunction "nRESET_4") (pintype "passive"))
    )
    (net (code "128") (name "unconnected-(U14-CSB-Pad7)") (class "Default")
      (node (ref "U14") (pin "7") (pinfunction "CSB_7") (pintype "passive"))
    )
    (net (code "129") (name "unconnected-(U14-NC-Pad4)") (class "Default")
      (node (ref "U14") (pin "4") (pinfunction "NC_4") (pintype "passive+no_connect"))
    )
    (net (code "130") (name "unconnected-(U16-X2-Pad15)") (class "Default")
      (node (ref "U16") (pin "15") (pinfunction "X2_15") (pintype "passive+no_connect"))
    )
    (net (code "131") (name "unconnected-(U16-X3-Pad11)") (class "Default")
      (node (ref "U16") (pin "11") (pinfunction "X3_11") (pintype "passive+no_connect"))
    )
    (net (code "132") (name "unconnected-(U16-Y2-Pad2)") (class "Default")
      (node (ref "U16") (pin "2") (pinfunction "Y2_2") (pintype "passive+no_connect"))
    )
    (net (code "133") (name "unconnected-(U16-Y3-Pad4)") (class "Default")
      (node (ref "U16") (pin "4") (pinfunction "Y3_4") (pintype "passive+no_connect"))
    )
  )
)
